# NN23_Det_Optode_02_OPA.net
KiCad netlist of a schematic drawn in EAGLE
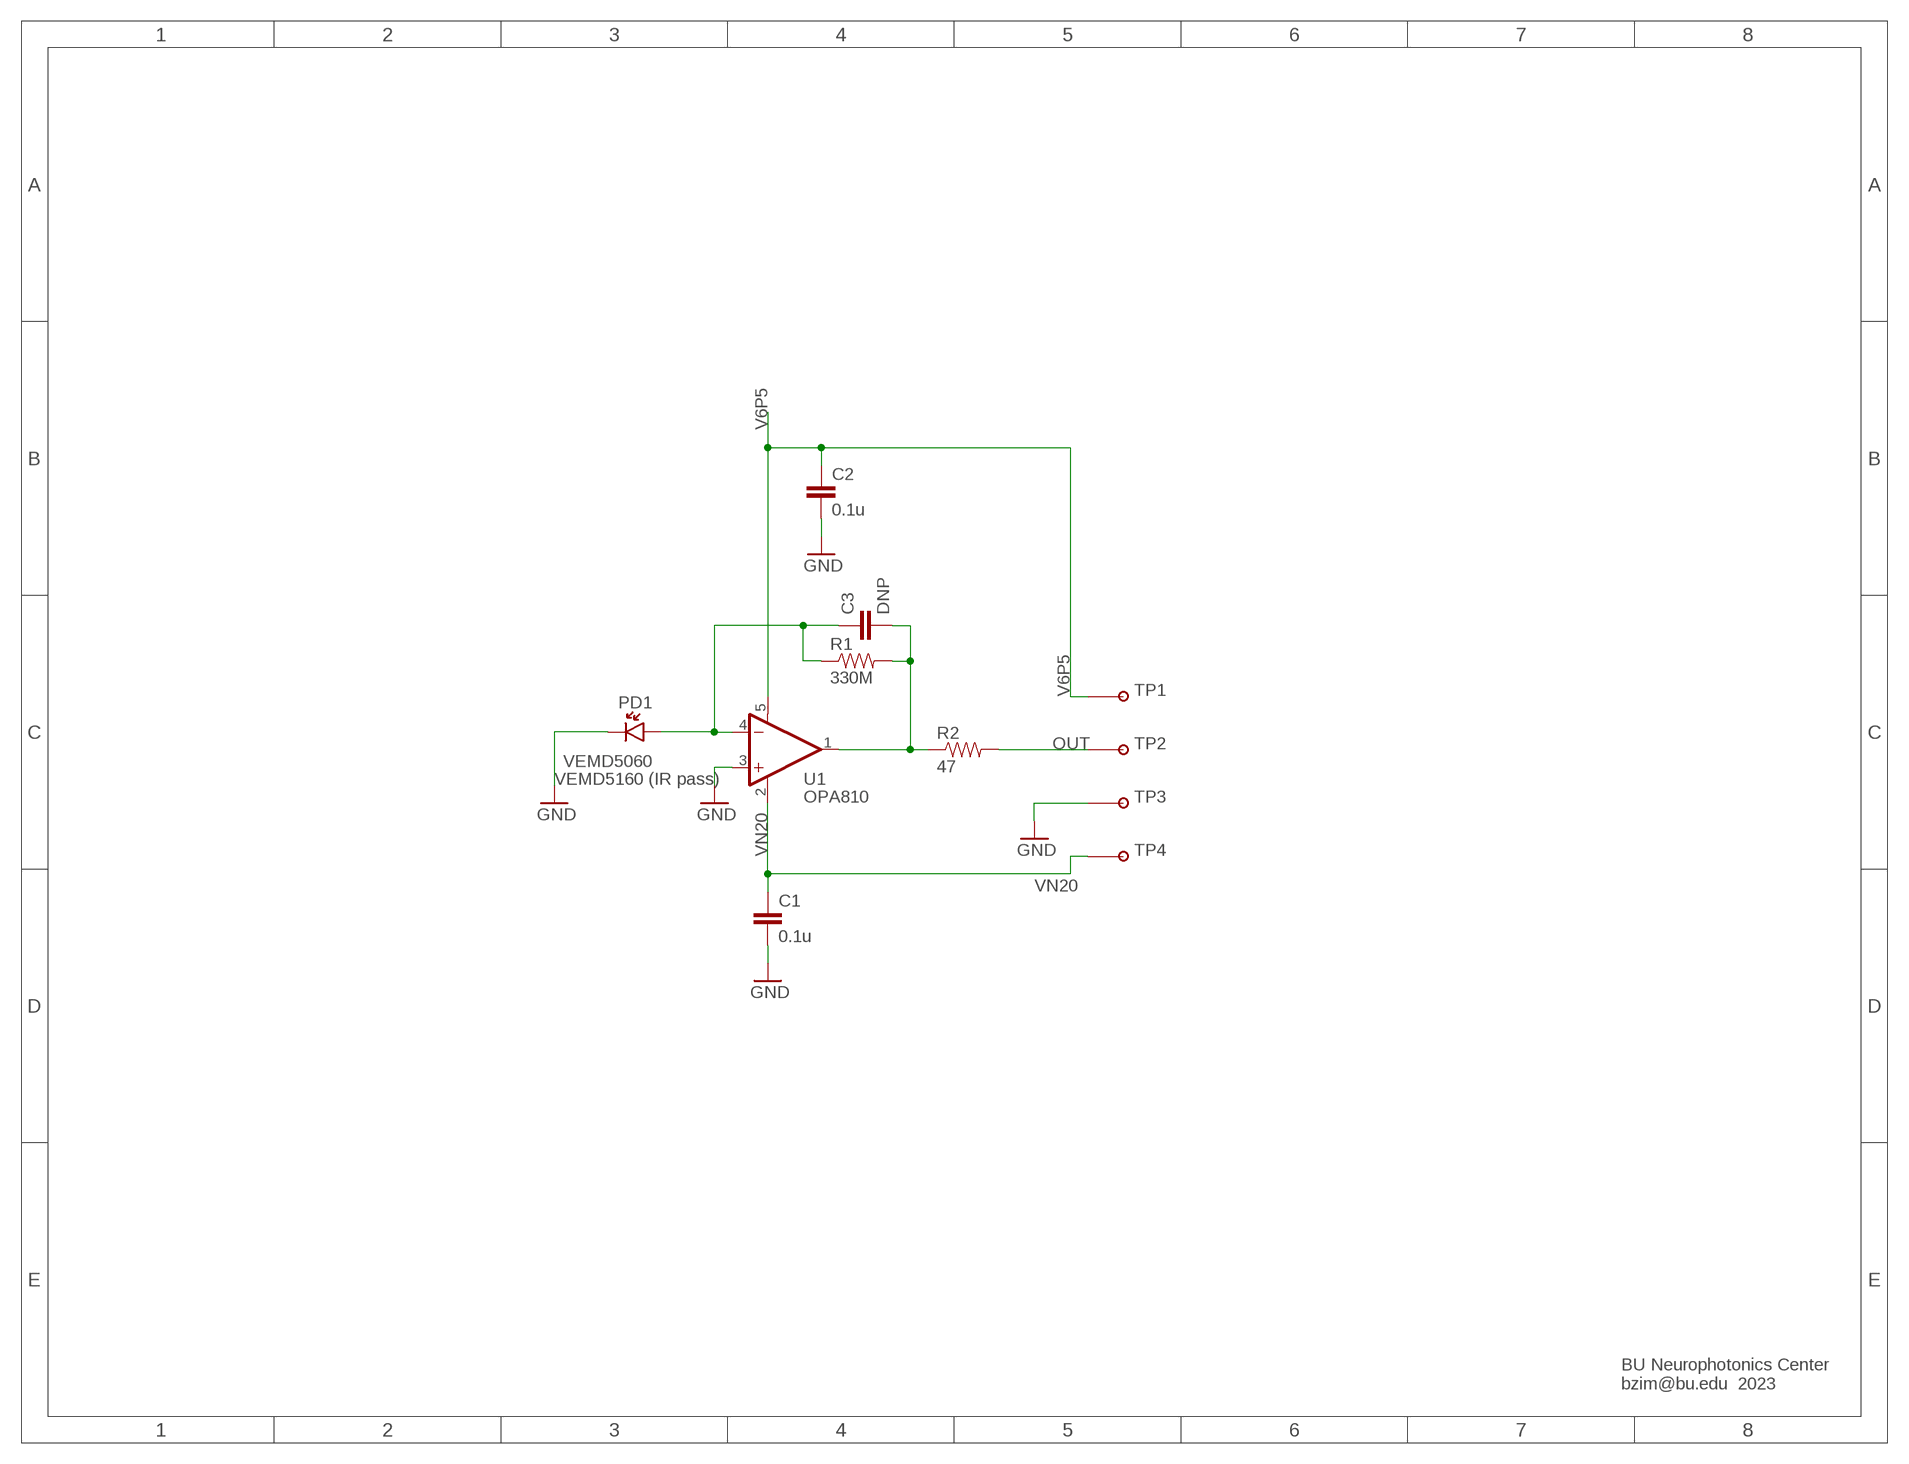
[diagram p0: schematic, sheet 1]

(export (version "E")
  (design (tool "Eeschema 10.0.6"))
  (components
    (comp (ref "C1")
      (value "0.1u")
      (footprint "eagle-import:0402-CAP")
      (libsource (lib "eagle-import") (part "CAP0402-CAP"))
    )
    (comp (ref "C2")
      (value "0.1u")
      (footprint "eagle-import:0402-CAP")
      (libsource (lib "eagle-import") (part "CAP0402-CAP"))
    )
    (comp (ref "C3")
      (value "DNP")
      (footprint "eagle-import:0402-CAP")
      (libsource (lib "eagle-import") (part "CAP0402-CAP"))
    )
    (comp (ref "PD1")
      (value "VEMD5060")
      (footprint "eagle-import:VEMD5060")
      (libsource (lib "eagle-import") (part "VEMD5060"))
    )
    (comp (ref "R1")
      (value "330M")
      (footprint "eagle-import:0402-RES")
      (libsource (lib "eagle-import") (part "RESISTOR0402-RES"))
    )
    (comp (ref "R2")
      (value "47")
      (footprint "eagle-import:0402-RES")
      (libsource (lib "eagle-import") (part "RESISTOR0402-RES"))
    )
    (comp (ref "TP1")
      (value "TESTPOINTPADSMALL")
      (footprint "eagle-import:TESTPAD_SMALL")
      (libsource (lib "eagle-import") (part "TESTPOINTPADSMALL"))
    )
    (comp (ref "TP2")
      (value "TESTPOINTPADSMALL")
      (footprint "eagle-import:TESTPAD_SMALL")
      (libsource (lib "eagle-import") (part "TESTPOINTPADSMALL"))
    )
    (comp (ref "TP3")
      (value "TESTPOINTPADSMALL")
      (footprint "eagle-import:TESTPAD_SMALL")
      (libsource (lib "eagle-import") (part "TESTPOINTPADSMALL"))
    )
    (comp (ref "TP4")
      (value "TESTPOINTPADSMALL")
      (footprint "eagle-import:TESTPAD_SMALL")
      (libsource (lib "eagle-import") (part "TESTPOINTPADSMALL"))
    )
    (comp (ref "U1")
      (value "OPA810")
      (footprint "eagle-import:SOT353")
      (libsource (lib "eagle-import") (part "OPA810"))
    )
  )
  (nets
    (net (code "1") (name "/OUT") (class "Default")
      (node (ref "R2") (pin "2") (pinfunction "2_2") (pintype "passive"))
      (node (ref "TP2") (pin "P$1") (pinfunction "P$1_P$1") (pintype "bidirectional"))
    )
    (net (code "2") (name "/V6P5") (class "Default")
      (node (ref "C2") (pin "1") (pinfunction "1_1") (pintype "passive"))
      (node (ref "TP1") (pin "P$1") (pinfunction "P$1_P$1") (pintype "bidirectional"))
      (node (ref "U1") (pin "5") (pinfunction "V+_5") (pintype "power_in"))
    )
    (net (code "3") (name "/VN20") (class "Default")
      (node (ref "C1") (pin "1") (pinfunction "1_1") (pintype "passive"))
      (node (ref "TP4") (pin "P$1") (pinfunction "P$1_P$1") (pintype "bidirectional"))
      (node (ref "U1") (pin "2") (pinfunction "V-_2") (pintype "power_in"))
    )
    (net (code "4") (name "GND") (class "Default")
      (node (ref "C1") (pin "2") (pinfunction "2_2") (pintype "passive"))
      (node (ref "C2") (pin "2") (pinfunction "2_2") (pintype "passive"))
      (node (ref "PD1") (pin "C1") (pinfunction "C_C1") (pintype "bidirectional"))
      (node (ref "PD1") (pin "C2") (pinfunction "C_C2") (pintype "bidirectional"))
      (node (ref "TP3") (pin "P$1") (pinfunction "P$1_P$1") (pintype "bidirectional"))
      (node (ref "U1") (pin "3") (pinfunction "+IN_3") (pintype "input"))
    )
    (net (code "5") (name "Net-(U1--IN)") (class "Default")
      (node (ref "C3") (pin "1") (pinfunction "1_1") (pintype "passive"))
      (node (ref "PD1") (pin "A") (pinfunction "A_A") (pintype "bidirectional"))
      (node (ref "R1") (pin "1") (pinfunction "1_1") (pintype "passive"))
      (node (ref "U1") (pin "4") (pinfunction "-IN_4") (pintype "input"))
    )
    (net (code "6") (name "Net-(U1-OUT)") (class "Default")
      (node (ref "C3") (pin "2") (pinfunction "2_2") (pintype "passive"))
      (node (ref "R1") (pin "2") (pinfunction "2_2") (pintype "passive"))
      (node (ref "R2") (pin "1") (pinfunction "1_1") (pintype "passive"))
      (node (ref "U1") (pin "1") (pinfunction "OUT_1") (pintype "output"))
    )
  )
)
